# Multi.net
KiCad netlist of a schematic drawn in EAGLE
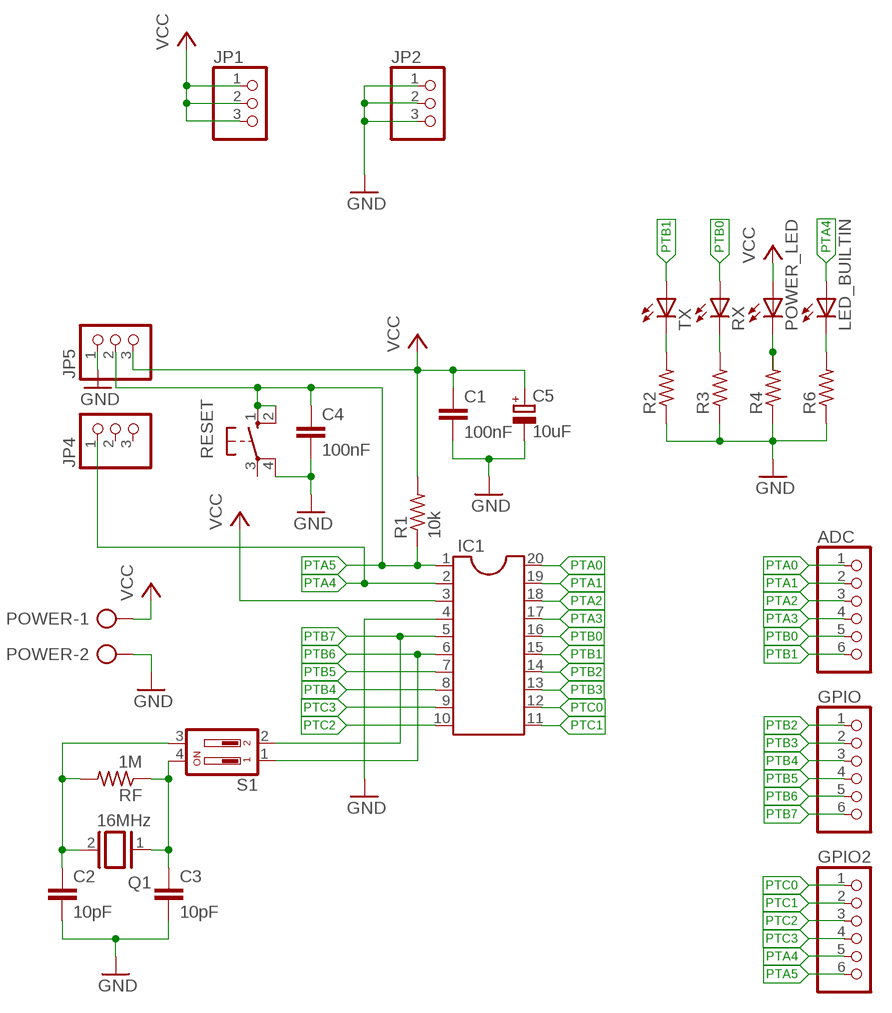
[diagram p0: schematic, sheet 1]

(export (version "E")
  (design (tool "Eeschema 10.0.6"))
  (components
    (comp (ref "ADC")
      (value "PINHD-1X6")
      (footprint "eagle-import:1X06")
      (libsource (lib "eagle-import") (part "PINHD-1X6"))
    )
    (comp (ref "C1")
      (value "100nF")
      (footprint "eagle-import:C025-025X050")
      (libsource (lib "eagle-import") (part "C-EU025-025X050"))
    )
    (comp (ref "C2")
      (value "10pF")
      (footprint "eagle-import:C025-025X050")
      (libsource (lib "eagle-import") (part "C-EU025-025X050"))
    )
    (comp (ref "C3")
      (value "10pF")
      (footprint "eagle-import:C025-025X050")
      (libsource (lib "eagle-import") (part "C-EU025-025X050"))
    )
    (comp (ref "C4")
      (value "100nF")
      (footprint "eagle-import:C025-025X050")
      (libsource (lib "eagle-import") (part "C-EU025-025X050"))
    )
    (comp (ref "C5")
      (value "10uF")
      (footprint "eagle-import:E2,5-6")
      (libsource (lib "eagle-import") (part "CPOL-EUE2.5-6"))
    )
    (comp (ref "GPIO")
      (value "PINHD-1X6")
      (footprint "eagle-import:1X06")
      (libsource (lib "eagle-import") (part "PINHD-1X6"))
    )
    (comp (ref "GPIO2")
      (value "PINHD-1X6")
      (footprint "eagle-import:1X06")
      (libsource (lib "eagle-import") (part "PINHD-1X6"))
    )
    (comp (ref "IC1")
      (value "DIL20S")
      (footprint "eagle-import:SOCKET-20")
      (libsource (lib "eagle-import") (part "DIL20S"))
    )
    (comp (ref "JP1")
      (value "PINHD-1X3")
      (footprint "eagle-import:1X03")
      (libsource (lib "eagle-import") (part "PINHD-1X3"))
    )
    (comp (ref "JP2")
      (value "PINHD-1X3")
      (footprint "eagle-import:1X03")
      (libsource (lib "eagle-import") (part "PINHD-1X3"))
    )
    (comp (ref "JP4")
      (value "PINHD-1X3")
      (footprint "eagle-import:1X03")
      (libsource (lib "eagle-import") (part "PINHD-1X3"))
    )
    (comp (ref "JP5")
      (value "PINHD-1X3")
      (footprint "eagle-import:1X03")
      (libsource (lib "eagle-import") (part "PINHD-1X3"))
    )
    (comp (ref "LED_BUILTIN")
      (value "LED3MM")
      (footprint "eagle-import:LED3MM")
      (libsource (lib "eagle-import") (part "LED3MM"))
    )
    (comp (ref "POWER")
      (value "AK500/2-H")
      (footprint "eagle-import:AK500_2-H")
      (libsource (lib "eagle-import") (part "AK500/2-H"))
    )
    (comp (ref "POWER_LED")
      (value "LED3MM")
      (footprint "eagle-import:LED3MM")
      (libsource (lib "eagle-import") (part "LED3MM"))
    )
    (comp (ref "Q1")
      (value "16MHz")
      (footprint "eagle-import:QS")
      (libsource (lib "eagle-import") (part "XTAL/S"))
    )
    (comp (ref "R1")
      (value "10k")
      (footprint "eagle-import:0207_7")
      (libsource (lib "eagle-import") (part "R-US_0207/7"))
    )
    (comp (ref "R2")
      (value "R-US_0207/7")
      (footprint "eagle-import:0207_7")
      (libsource (lib "eagle-import") (part "R-US_0207/7"))
    )
    (comp (ref "R3")
      (value "R-US_0207/7")
      (footprint "eagle-import:0207_7")
      (libsource (lib "eagle-import") (part "R-US_0207/7"))
    )
    (comp (ref "R4")
      (value "R-US_0207/7")
      (footprint "eagle-import:0207_7")
      (libsource (lib "eagle-import") (part "R-US_0207/7"))
    )
    (comp (ref "R6")
      (value "R-US_0207/7")
      (footprint "eagle-import:0207_7")
      (libsource (lib "eagle-import") (part "R-US_0207/7"))
    )
    (comp (ref "RESET")
      (value "10-XX")
      (footprint "eagle-import:B3F-10XX")
      (fields (field (name "MPN") "B3F-1000"))
      (libsource (lib "eagle-import") (part "10-XX"))
    )
    (comp (ref "RF")
      (value "1M")
      (footprint "eagle-import:0207_7")
      (libsource (lib "eagle-import") (part "R-US_0207/7"))
    )
    (comp (ref "RX")
      (value "LED3MM")
      (footprint "eagle-import:LED3MM")
      (libsource (lib "eagle-import") (part "LED3MM"))
    )
    (comp (ref "S1")
      (value "DS02")
      (footprint "eagle-import:DS-02")
      (libsource (lib "eagle-import") (part "DS02"))
    )
    (comp (ref "TX")
      (value "LED3MM")
      (footprint "eagle-import:LED3MM")
      (libsource (lib "eagle-import") (part "LED3MM"))
    )
  )
  (nets
    (net (code "1") (name "GND") (class "Default")
      (node (ref "C1") (pin "2") (pinfunction "2_2") (pintype "passive"))
      (node (ref "C2") (pin "2") (pinfunction "2_2") (pintype "passive"))
      (node (ref "C3") (pin "2") (pinfunction "2_2") (pintype "passive"))
      (node (ref "C4") (pin "2") (pinfunction "2_2") (pintype "passive"))
      (node (ref "C5") (pin "-") (pinfunction "-_-") (pintype "passive"))
      (node (ref "IC1") (pin "4") (pinfunction "4_4") (pintype "passive"))
      (node (ref "JP2") (pin "1") (pinfunction "1_1") (pintype "passive"))
      (node (ref "JP2") (pin "2") (pinfunction "2_2") (pintype "passive"))
      (node (ref "JP2") (pin "3") (pinfunction "3_3") (pintype "passive"))
      (node (ref "JP5") (pin "1") (pinfunction "1_1") (pintype "passive"))
      (node (ref "POWER") (pin "2") (pinfunction "KL_2") (pintype "passive"))
      (node (ref "R2") (pin "1") (pinfunction "1_1") (pintype "passive"))
      (node (ref "R3") (pin "1") (pinfunction "1_1") (pintype "passive"))
      (node (ref "R4") (pin "1") (pinfunction "1_1") (pintype "passive"))
      (node (ref "R6") (pin "1") (pinfunction "1_1") (pintype "passive"))
      (node (ref "RESET") (pin "4") (pinfunction "P1_4") (pintype "passive"))
    )
    (net (code "2") (name "Net-(C2-Pad1)") (class "Default")
      (node (ref "C2") (pin "1") (pinfunction "1_1") (pintype "passive"))
      (node (ref "Q1") (pin "2") (pinfunction "2_2") (pintype "passive"))
      (node (ref "RF") (pin "2") (pinfunction "2_2") (pintype "passive"))
      (node (ref "S1") (pin "3") (pinfunction "3_3") (pintype "passive"))
    )
    (net (code "3") (name "Net-(C3-Pad1)") (class "Default")
      (node (ref "C3") (pin "1") (pinfunction "1_1") (pintype "passive"))
      (node (ref "Q1") (pin "1") (pinfunction "1_1") (pintype "passive"))
      (node (ref "RF") (pin "1") (pinfunction "1_1") (pintype "passive"))
      (node (ref "S1") (pin "4") (pinfunction "4_4") (pintype "passive"))
    )
    (net (code "4") (name "Net-(LED_BUILTIN-C)") (class "Default")
      (node (ref "LED_BUILTIN") (pin "K") (pinfunction "C_K") (pintype "passive"))
      (node (ref "R6") (pin "2") (pinfunction "2_2") (pintype "passive"))
    )
    (net (code "5") (name "Net-(POWER_LED-C)") (class "Default")
      (node (ref "POWER_LED") (pin "K") (pinfunction "C_K") (pintype "passive"))
      (node (ref "R4") (pin "2") (pinfunction "2_2") (pintype "passive"))
    )
    (net (code "6") (name "Net-(RX-C)") (class "Default")
      (node (ref "R3") (pin "2") (pinfunction "2_2") (pintype "passive"))
      (node (ref "RX") (pin "K") (pinfunction "C_K") (pintype "passive"))
    )
    (net (code "7") (name "Net-(TX-C)") (class "Default")
      (node (ref "R2") (pin "2") (pinfunction "2_2") (pintype "passive"))
      (node (ref "TX") (pin "K") (pinfunction "C_K") (pintype "passive"))
    )
    (net (code "8") (name "PTA0") (class "Default")
      (node (ref "ADC") (pin "1") (pinfunction "1_1") (pintype "passive"))
      (node (ref "IC1") (pin "20") (pinfunction "20_20") (pintype "passive"))
    )
    (net (code "9") (name "PTA1") (class "Default")
      (node (ref "ADC") (pin "2") (pinfunction "2_2") (pintype "passive"))
      (node (ref "IC1") (pin "19") (pinfunction "19_19") (pintype "passive"))
    )
    (net (code "10") (name "PTA2") (class "Default")
      (node (ref "ADC") (pin "3") (pinfunction "3_3") (pintype "passive"))
      (node (ref "IC1") (pin "18") (pinfunction "18_18") (pintype "passive"))
    )
    (net (code "11") (name "PTA3") (class "Default")
      (node (ref "ADC") (pin "4") (pinfunction "4_4") (pintype "passive"))
      (node (ref "IC1") (pin "17") (pinfunction "17_17") (pintype "passive"))
    )
    (net (code "12") (name "PTA4") (class "Default")
      (node (ref "GPIO2") (pin "5") (pinfunction "5_5") (pintype "passive"))
      (node (ref "IC1") (pin "2") (pinfunction "2_2") (pintype "passive"))
      (node (ref "JP4") (pin "1") (pinfunction "1_1") (pintype "passive"))
      (node (ref "LED_BUILTIN") (pin "A") (pinfunction "A_A") (pintype "passive"))
    )
    (net (code "13") (name "PTA5") (class "Default")
      (node (ref "C4") (pin "1") (pinfunction "1_1") (pintype "passive"))
      (node (ref "GPIO2") (pin "6") (pinfunction "6_6") (pintype "passive"))
      (node (ref "IC1") (pin "1") (pinfunction "1_1") (pintype "passive"))
      (node (ref "JP5") (pin "2") (pinfunction "2_2") (pintype "passive"))
      (node (ref "R1") (pin "1") (pinfunction "1_1") (pintype "passive"))
      (node (ref "RESET") (pin "1") (pinfunction "S_1") (pintype "passive"))
      (node (ref "RESET") (pin "2") (pinfunction "S1_2") (pintype "passive"))
    )
    (net (code "14") (name "PTB0") (class "Default")
      (node (ref "ADC") (pin "5") (pinfunction "5_5") (pintype "passive"))
      (node (ref "IC1") (pin "16") (pinfunction "16_16") (pintype "passive"))
      (node (ref "RX") (pin "A") (pinfunction "A_A") (pintype "passive"))
    )
    (net (code "15") (name "PTB1") (class "Default")
      (node (ref "ADC") (pin "6") (pinfunction "6_6") (pintype "passive"))
      (node (ref "IC1") (pin "15") (pinfunction "15_15") (pintype "passive"))
      (node (ref "TX") (pin "A") (pinfunction "A_A") (pintype "passive"))
    )
    (net (code "16") (name "PTB2") (class "Default")
      (node (ref "GPIO") (pin "1") (pinfunction "1_1") (pintype "passive"))
      (node (ref "IC1") (pin "14") (pinfunction "14_14") (pintype "passive"))
    )
    (net (code "17") (name "PTB3") (class "Default")
      (node (ref "GPIO") (pin "2") (pinfunction "2_2") (pintype "passive"))
      (node (ref "IC1") (pin "13") (pinfunction "13_13") (pintype "passive"))
    )
    (net (code "18") (name "PTB4") (class "Default")
      (node (ref "GPIO") (pin "3") (pinfunction "3_3") (pintype "passive"))
      (node (ref "IC1") (pin "8") (pinfunction "8_8") (pintype "passive"))
    )
    (net (code "19") (name "PTB5") (class "Default")
      (node (ref "GPIO") (pin "4") (pinfunction "4_4") (pintype "passive"))
      (node (ref "IC1") (pin "7") (pinfunction "7_7") (pintype "passive"))
    )
    (net (code "20") (name "PTB6") (class "Default")
      (node (ref "GPIO") (pin "5") (pinfunction "5_5") (pintype "passive"))
      (node (ref "IC1") (pin "6") (pinfunction "6_6") (pintype "passive"))
      (node (ref "S1") (pin "1") (pinfunction "1_1") (pintype "passive"))
    )
    (net (code "21") (name "PTB7") (class "Default")
      (node (ref "GPIO") (pin "6") (pinfunction "6_6") (pintype "passive"))
      (node (ref "IC1") (pin "5") (pinfunction "5_5") (pintype "passive"))
      (node (ref "S1") (pin "2") (pinfunction "2_2") (pintype "passive"))
    )
    (net (code "22") (name "PTC0") (class "Default")
      (node (ref "GPIO2") (pin "1") (pinfunction "1_1") (pintype "passive"))
      (node (ref "IC1") (pin "12") (pinfunction "12_12") (pintype "passive"))
    )
    (net (code "23") (name "PTC1") (class "Default")
      (node (ref "GPIO2") (pin "2") (pinfunction "2_2") (pintype "passive"))
      (node (ref "IC1") (pin "11") (pinfunction "11_11") (pintype "passive"))
    )
    (net (code "24") (name "PTC2") (class "Default")
      (node (ref "GPIO2") (pin "3") (pinfunction "3_3") (pintype "passive"))
      (node (ref "IC1") (pin "10") (pinfunction "10_10") (pintype "passive"))
    )
    (net (code "25") (name "PTC3") (class "Default")
      (node (ref "GPIO2") (pin "4") (pinfunction "4_4") (pintype "passive"))
      (node (ref "IC1") (pin "9") (pinfunction "9_9") (pintype "passive"))
    )
    (net (code "26") (name "VCC") (class "Default")
      (node (ref "C1") (pin "1") (pinfunction "1_1") (pintype "passive"))
      (node (ref "C5") (pin "+") (pinfunction "+_+") (pintype "passive"))
      (node (ref "IC1") (pin "3") (pinfunction "3_3") (pintype "passive"))
      (node (ref "JP1") (pin "1") (pinfunction "1_1") (pintype "passive"))
      (node (ref "JP1") (pin "2") (pinfunction "2_2") (pintype "passive"))
      (node (ref "JP1") (pin "3") (pinfunction "3_3") (pintype "passive"))
      (node (ref "JP5") (pin "3") (pinfunction "3_3") (pintype "passive"))
      (node (ref "POWER") (pin "1") (pinfunction "KL_1") (pintype "passive"))
      (node (ref "POWER_LED") (pin "A") (pinfunction "A_A") (pintype "passive"))
      (node (ref "R1") (pin "2") (pinfunction "2_2") (pintype "passive"))
    )
    (net (code "27") (name "unconnected-(JP4-Pad2)") (class "Default")
      (node (ref "JP4") (pin "2") (pinfunction "2_2") (pintype "passive"))
    )
    (net (code "28") (name "unconnected-(JP4-Pad3)") (class "Default")
      (node (ref "JP4") (pin "3") (pinfunction "3_3") (pintype "passive"))
    )
    (net (code "29") (name "unconnected-(RESET-P-Pad3)") (class "Default")
      (node (ref "RESET") (pin "3") (pinfunction "P_3") (pintype "passive"))
    )
  )
)
